# stm32custompcb_schematic.net
KiCad netlist of a schematic drawn in Altium Designer
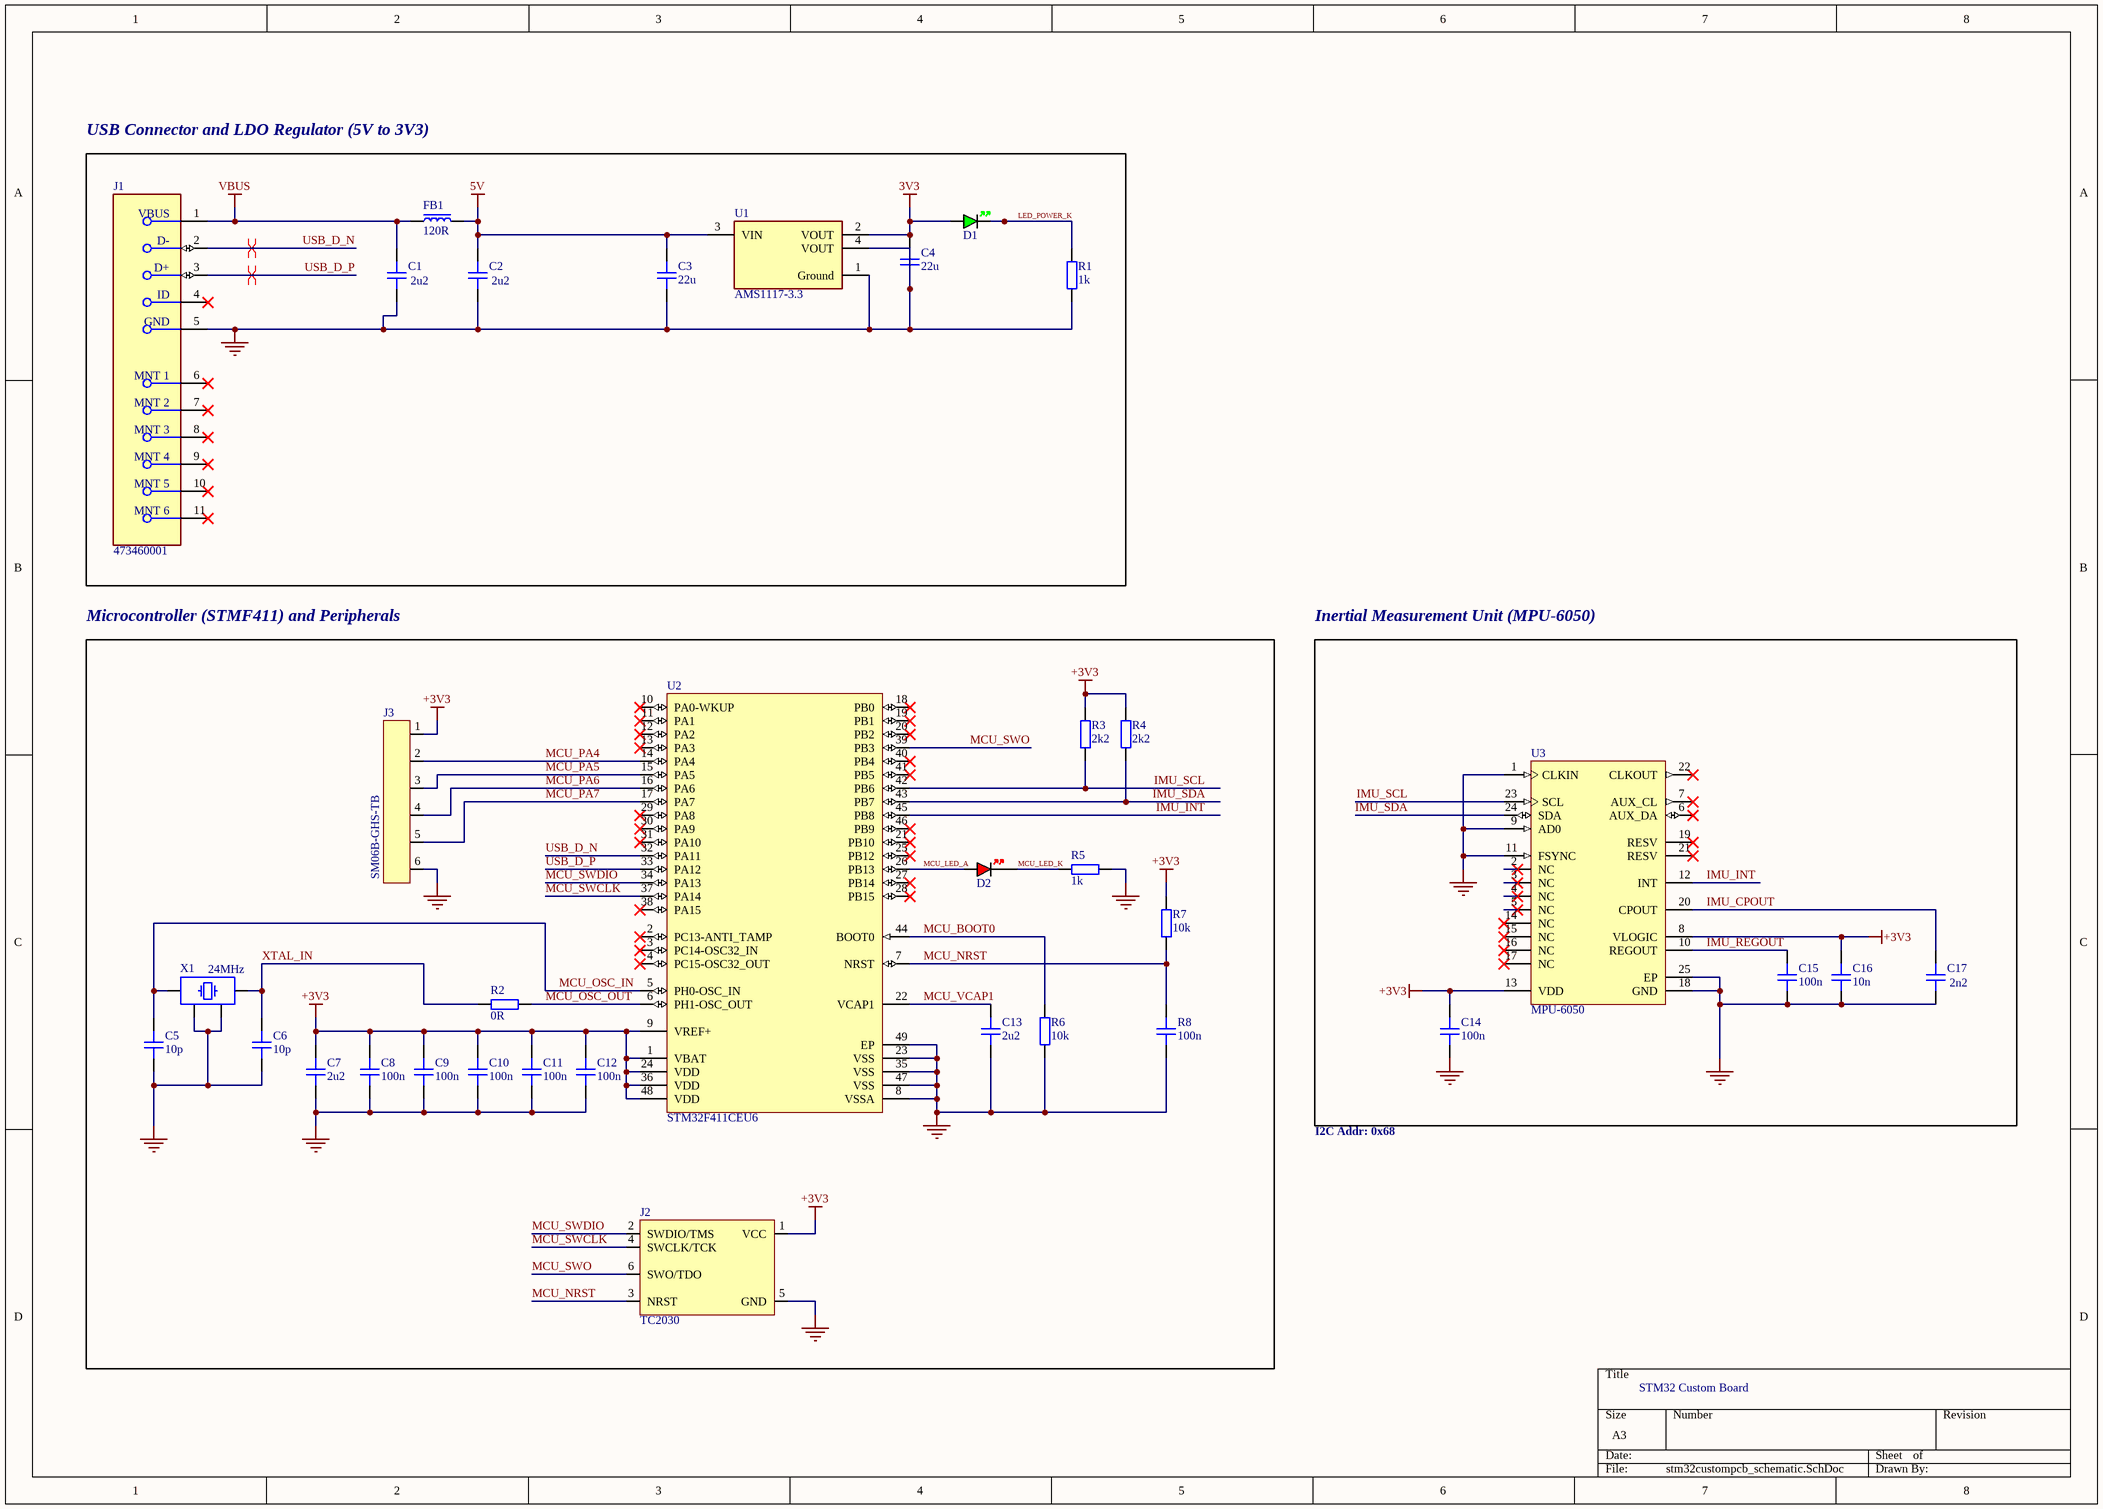
[diagram p0: stm32custompcb_schematic.SchDoc]

(export (version "E")
  (design (tool "Eeschema 10.0.6"))
  (components
    (comp (ref "C1")
      (value "2u2")
      (footprint "CAP_0402")
      (description "Capacitor SMD 0402")
      (libsource (lib "Schematic-Lib-PhilsLab") (part "CAP_0402"))
    )
    (comp (ref "C2")
      (value "2u2")
      (footprint "CAP_0402")
      (description "Capacitor SMD 0402")
      (libsource (lib "Schematic-Lib-PhilsLab") (part "CAP_0402"))
    )
    (comp (ref "C3")
      (value "22u")
      (footprint "CAP_0805")
      (description "Capacitor SMD 0805")
      (libsource (lib "Schematic-Lib-PhilsLab") (part "CAP_0805"))
    )
    (comp (ref "C4")
      (value "22u")
      (footprint "CAP_0805")
      (description "Capacitor SMD 0805")
      (libsource (lib "Schematic-Lib-PhilsLab") (part "CAP_0805"))
    )
    (comp (ref "C5")
      (value "10p")
      (footprint "CAP_0402")
      (description "Capacitor SMD 0402")
      (libsource (lib "Schematic-Lib-PhilsLab") (part "CAP_0402"))
    )
    (comp (ref "C6")
      (value "10p")
      (footprint "CAP_0402")
      (description "Capacitor SMD 0402")
      (libsource (lib "Schematic-Lib-PhilsLab") (part "CAP_0402"))
    )
    (comp (ref "C7")
      (value "2u2")
      (footprint "CAP_0603")
      (description "Capacitor SMD 0603")
      (libsource (lib "Schematic-Lib-PhilsLab") (part "CAP_0603"))
    )
    (comp (ref "C8")
      (value "100n")
      (footprint "CAP_0402")
      (description "Capacitor SMD 0402")
      (libsource (lib "Schematic-Lib-PhilsLab") (part "CAP_0402"))
    )
    (comp (ref "C9")
      (value "100n")
      (footprint "CAP_0402")
      (description "Capacitor SMD 0402")
      (libsource (lib "Schematic-Lib-PhilsLab") (part "CAP_0402"))
    )
    (comp (ref "C10")
      (value "100n")
      (footprint "CAP_0402")
      (description "Capacitor SMD 0402")
      (libsource (lib "Schematic-Lib-PhilsLab") (part "CAP_0402"))
    )
    (comp (ref "C11")
      (value "100n")
      (footprint "CAP_0402")
      (description "Capacitor SMD 0402")
      (libsource (lib "Schematic-Lib-PhilsLab") (part "CAP_0402"))
    )
    (comp (ref "C12")
      (value "100n")
      (footprint "CAP_0402")
      (description "Capacitor SMD 0402")
      (libsource (lib "Schematic-Lib-PhilsLab") (part "CAP_0402"))
    )
    (comp (ref "C13")
      (value "2u2")
      (footprint "CAP_0603")
      (description "Capacitor SMD 0603")
      (libsource (lib "Schematic-Lib-PhilsLab") (part "CAP_0603"))
    )
    (comp (ref "C14")
      (value "100n")
      (footprint "CAP_0402")
      (description "Capacitor SMD 0402")
      (libsource (lib "Schematic-Lib-PhilsLab") (part "CAP_0402"))
    )
    (comp (ref "C15")
      (value "100n")
      (footprint "CAP_0402")
      (description "Capacitor SMD 0402")
      (libsource (lib "Schematic-Lib-PhilsLab") (part "CAP_0402"))
    )
    (comp (ref "C16")
      (value "10n")
      (footprint "CAP_0402")
      (description "Capacitor SMD 0402")
      (libsource (lib "Schematic-Lib-PhilsLab") (part "CAP_0402"))
    )
    (comp (ref "C17")
      (value "2n2")
      (footprint "CAP_0402")
      (description "Capacitor SMD 0402")
      (libsource (lib "Schematic-Lib-PhilsLab") (part "CAP_0402"))
    )
    (comp (ref "D1")
      (value "GREEN")
      (footprint "LED_0402_GREEN")
      (description "LED 0402 GREEN SMD")
      (libsource (lib "Schematic-Lib-PhilsLab") (part "LED_0402_GREEN"))
    )
    (comp (ref "D2")
      (value "RED")
      (footprint "LED_0402_RED")
      (description "LED 0402 RED SMD")
      (libsource (lib "Schematic-Lib-PhilsLab") (part "LED_0402_RED"))
    )
    (comp (ref "FB1")
      (value "120R")
      (footprint "FB_0603")
      (description "Ferrite Bead SMD 0603")
      (libsource (lib "Schematic-Lib-PhilsLab") (part "FB_0603"))
    )
    (comp (ref "J1")
      (value "473460001")
      (footprint "FP-473460001-MFG")
      (description "CONN RCPT USB2.0 MICRO B SMD R/A")
      (fields
        (field (name "OCTOPART") "https://octopart.com/47346-0001-molex-7164928")
        (field (name "MANUFACTURER") "Molex")
      )
      (libsource (lib "Altium Content Vault") (part "53ae1f1d9b557310b43ca686e5bb76a"))
    )
    (comp (ref "J2")
      (value "TC2030")
      (footprint "TC2030-FP")
      (description "Tag-Connect No-Solder SWD Debug Connector DO NOT PLACE")
      (fields (field (name "MANUFACTURER") "Tag-Connect"))
      (libsource (lib "Schematic-Lib-PhilsLab") (part "TC2030"))
    )
    (comp (ref "J3")
      (value "SM06B-GHS-TB")
      (footprint "SM06B-GHS-TB")
      (description "Header Connector 6 Position 1.25MM Pitch SMD Horizontal JST GH")
      (fields (field (name "MANUFACTURER") "JST"))
      (libsource (lib "Schematic-Lib-PhilsLab") (part "SM06B-GHS-TB"))
    )
    (comp (ref "R1")
      (value "1k")
      (footprint "RES_0402")
      (description "Resistor SMD 0402")
      (libsource (lib "Schematic-Lib-PhilsLab") (part "RES_0402"))
    )
    (comp (ref "R2")
      (value "0R")
      (footprint "RES_0402")
      (description "Resistor SMD 0402")
      (libsource (lib "Schematic-Lib-PhilsLab") (part "RES_0402"))
    )
    (comp (ref "R3")
      (value "2k2")
      (footprint "RES_0402")
      (description "Resistor SMD 0402")
      (libsource (lib "Schematic-Lib-PhilsLab") (part "RES_0402"))
    )
    (comp (ref "R4")
      (value "2k2")
      (footprint "RES_0402")
      (description "Resistor SMD 0402")
      (libsource (lib "Schematic-Lib-PhilsLab") (part "RES_0402"))
    )
    (comp (ref "R5")
      (value "1k")
      (footprint "RES_0402")
      (description "Resistor SMD 0402")
      (libsource (lib "Schematic-Lib-PhilsLab") (part "RES_0402"))
    )
    (comp (ref "R6")
      (value "10k")
      (footprint "RES_0402")
      (description "Resistor SMD 0402")
      (libsource (lib "Schematic-Lib-PhilsLab") (part "RES_0402"))
    )
    (comp (ref "R7")
      (value "10k")
      (footprint "RES_0402")
      (description "Resistor SMD 0402")
      (libsource (lib "Schematic-Lib-PhilsLab") (part "RES_0402"))
    )
    (comp (ref "R8")
      (value "100n")
      (footprint "CAP_0402")
      (description "Capacitor SMD 0402")
      (libsource (lib "Schematic-Lib-PhilsLab") (part "CAP_0402"))
    )
    (comp (ref "U1")
      (value "AMS1117-3.3")
      (footprint "FP-AMS1117-IPC_C")
      (description "LDO Voltage Regulators 1A, 3.3V")
      (fields
        (field (name "OCTOPART") "https://octopart.com/ams1117-3.3-advanced+monolithic+systems-25899300")
        (field (name "MANUFACTURER") "Advanced Monolithic Systems")
      )
      (libsource (lib "Altium Content Vault") (part "8bdbb5f8e77002000e30dd2845d0354"))
    )
    (comp (ref "U2")
      (value "STM32F411CEU6")
      (footprint "STM-UFQFPN48_L")
      (libsource (lib "Altium Content Vault") (part "MC-ARM-STM32F411-UFQFPN48"))
    )
    (comp (ref "U3")
      (value "MPU-6050")
      (footprint "IS-QFN-24_V")
      (fields (field (name "MANUFACTURER") "InvenSense"))
      (libsource (lib "Altium Content Vault") (part "IS-MPU-6050-QFN-24"))
    )
    (comp (ref "X1")
      (value "24MHz")
      (footprint "XTAL_3225")
      (description "Crystal SMD 24MHz 10PPM 7pF 3225")
      (fields
        (field (name "MANUFACTURER") "Epson")
        (field (name "MANUFACTURER PART NUMBER") "TSX-3225 24.0000MF15X-AC")
      )
      (libsource (lib "Schematic-Lib-PhilsLab") (part "TSX-3225_24.0000MF15X-AC"))
    )
  )
  (nets
    (net (code "1") (name "+3V3") (class "Default")
      (node (ref "C10") (pin "2") (pinfunction "2_2") (pintype "passive"))
      (node (ref "C11") (pin "2") (pinfunction "2_2") (pintype "passive"))
      (node (ref "C12") (pin "2") (pinfunction "2_2") (pintype "passive"))
      (node (ref "C14") (pin "2") (pinfunction "2_2") (pintype "passive"))
      (node (ref "C16") (pin "2") (pinfunction "2_2") (pintype "passive"))
      (node (ref "C7") (pin "1") (pinfunction "1_1") (pintype "passive"))
      (node (ref "C8") (pin "2") (pinfunction "2_2") (pintype "passive"))
      (node (ref "C9") (pin "2") (pinfunction "2_2") (pintype "passive"))
      (node (ref "J2") (pin "1") (pinfunction "VCC_1") (pintype "passive"))
      (node (ref "J3") (pin "1") (pinfunction "1_1") (pintype "passive"))
      (node (ref "R3") (pin "2") (pinfunction "2_2") (pintype "passive"))
      (node (ref "R4") (pin "2") (pinfunction "2_2") (pintype "passive"))
      (node (ref "R7") (pin "2") (pinfunction "2_2") (pintype "passive"))
      (node (ref "U2") (pin "1") (pinfunction "VBAT_1") (pintype "power_in"))
      (node (ref "U2") (pin "24") (pinfunction "VDD_24") (pintype "power_in"))
      (node (ref "U2") (pin "36") (pinfunction "VDD_36") (pintype "power_in"))
      (node (ref "U2") (pin "48") (pinfunction "VDD_48") (pintype "power_in"))
      (node (ref "U2") (pin "9") (pinfunction "VREF+_9") (pintype "power_in"))
      (node (ref "U3") (pin "13") (pinfunction "VDD_13") (pintype "power_in"))
      (node (ref "U3") (pin "8") (pinfunction "VLOGIC_8") (pintype "power_in"))
    )
    (net (code "2") (name "/IMU_CPOUT") (class "Default")
      (node (ref "C17") (pin "2") (pinfunction "2_2") (pintype "passive"))
      (node (ref "U3") (pin "20") (pinfunction "CPOUT_20") (pintype "passive"))
    )
    (net (code "3") (name "/IMU_INT") (class "Default")
      (node (ref "U2") (pin "45") (pinfunction "PB8_45") (pintype "bidirectional"))
      (node (ref "U3") (pin "12") (pinfunction "INT_12") (pintype "open_collector"))
    )
    (net (code "4") (name "/IMU_REGOUT") (class "Default")
      (node (ref "C15") (pin "2") (pinfunction "2_2") (pintype "passive"))
      (node (ref "U3") (pin "10") (pinfunction "REGOUT_10") (pintype "passive"))
    )
    (net (code "5") (name "/IMU_SCL") (class "Default")
      (node (ref "R3") (pin "1") (pinfunction "1_1") (pintype "passive"))
      (node (ref "U2") (pin "42") (pinfunction "PB6_42") (pintype "bidirectional"))
      (node (ref "U3") (pin "23") (pinfunction "SCL_23") (pintype "input"))
    )
    (net (code "6") (name "/IMU_SDA") (class "Default")
      (node (ref "R4") (pin "1") (pinfunction "1_1") (pintype "passive"))
      (node (ref "U2") (pin "43") (pinfunction "PB7_43") (pintype "bidirectional"))
      (node (ref "U3") (pin "24") (pinfunction "SDA_24") (pintype "bidirectional"))
    )
    (net (code "7") (name "/LED_POWER_K") (class "Default")
      (node (ref "D1") (pin "K") (pinfunction "K_K") (pintype "passive"))
      (node (ref "R1") (pin "2") (pinfunction "2_2") (pintype "passive"))
    )
    (net (code "8") (name "/MCU_BOOT0") (class "Default")
      (node (ref "R6") (pin "2") (pinfunction "2_2") (pintype "passive"))
      (node (ref "U2") (pin "44") (pinfunction "BOOT0_44") (pintype "input"))
    )
    (net (code "9") (name "/MCU_LED_A") (class "Default")
      (node (ref "D2") (pin "A") (pinfunction "A_A") (pintype "passive"))
      (node (ref "U2") (pin "26") (pinfunction "PB13_26") (pintype "bidirectional"))
    )
    (net (code "10") (name "/MCU_LED_K") (class "Default")
      (node (ref "D2") (pin "K") (pinfunction "K_K") (pintype "passive"))
      (node (ref "R5") (pin "2") (pinfunction "2_2") (pintype "passive"))
    )
    (net (code "11") (name "/MCU_NRST") (class "Default")
      (node (ref "J2") (pin "3") (pinfunction "NRST_3") (pintype "passive"))
      (node (ref "R7") (pin "1") (pinfunction "1_1") (pintype "passive"))
      (node (ref "R8") (pin "2") (pinfunction "2_2") (pintype "passive"))
      (node (ref "U2") (pin "7") (pinfunction "NRST_7") (pintype "bidirectional"))
    )
    (net (code "12") (name "/MCU_OSC_IN") (class "Default")
      (node (ref "C5") (pin "2") (pinfunction "2_2") (pintype "passive"))
      (node (ref "U2") (pin "5") (pinfunction "PH0-OSC_IN_5") (pintype "bidirectional"))
      (node (ref "X1") (pin "1") (pinfunction "1_1") (pintype "passive"))
    )
    (net (code "13") (name "/MCU_OSC_OUT") (class "Default")
      (node (ref "R2") (pin "2") (pinfunction "2_2") (pintype "passive"))
      (node (ref "U2") (pin "6") (pinfunction "PH1-OSC_OUT_6") (pintype "bidirectional"))
    )
    (net (code "14") (name "/MCU_PA4") (class "Default")
      (node (ref "J3") (pin "2") (pinfunction "2_2") (pintype "passive"))
      (node (ref "U2") (pin "14") (pinfunction "PA4_14") (pintype "bidirectional"))
    )
    (net (code "15") (name "/MCU_PA5") (class "Default")
      (node (ref "J3") (pin "3") (pinfunction "3_3") (pintype "passive"))
      (node (ref "U2") (pin "15") (pinfunction "PA5_15") (pintype "bidirectional"))
    )
    (net (code "16") (name "/MCU_PA6") (class "Default")
      (node (ref "J3") (pin "4") (pinfunction "4_4") (pintype "passive"))
      (node (ref "U2") (pin "16") (pinfunction "PA6_16") (pintype "bidirectional"))
    )
    (net (code "17") (name "/MCU_PA7") (class "Default")
      (node (ref "J3") (pin "5") (pinfunction "5_5") (pintype "passive"))
      (node (ref "U2") (pin "17") (pinfunction "PA7_17") (pintype "bidirectional"))
    )
    (net (code "18") (name "/MCU_SWCLK") (class "Default")
      (node (ref "J2") (pin "4") (pinfunction "SWCLK/TCK_4") (pintype "passive"))
      (node (ref "U2") (pin "37") (pinfunction "PA14_37") (pintype "bidirectional"))
    )
    (net (code "19") (name "/MCU_SWDIO") (class "Default")
      (node (ref "J2") (pin "2") (pinfunction "SWDIO/TMS_2") (pintype "passive"))
      (node (ref "U2") (pin "34") (pinfunction "PA13_34") (pintype "bidirectional"))
    )
    (net (code "20") (name "/MCU_SWO") (class "Default")
      (node (ref "J2") (pin "6") (pinfunction "SWO/TDO_6") (pintype "passive"))
      (node (ref "U2") (pin "39") (pinfunction "PB3_39") (pintype "bidirectional"))
    )
    (net (code "21") (name "/MCU_VCAP1") (class "Default")
      (node (ref "C13") (pin "1") (pinfunction "1_1") (pintype "passive"))
      (node (ref "U2") (pin "22") (pinfunction "VCAP1_22") (pintype "passive"))
    )
    (net (code "22") (name "/USB_D_N") (class "Default")
      (node (ref "J1") (pin "2") (pinfunction "D-_2") (pintype "bidirectional"))
      (node (ref "U2") (pin "32") (pinfunction "PA11_32") (pintype "bidirectional"))
    )
    (net (code "23") (name "/USB_D_P") (class "Default")
      (node (ref "J1") (pin "3") (pinfunction "D+_3") (pintype "bidirectional"))
      (node (ref "U2") (pin "33") (pinfunction "PA12_33") (pintype "bidirectional"))
    )
    (net (code "24") (name "/XTAL_IN") (class "Default")
      (node (ref "C6") (pin "2") (pinfunction "2_2") (pintype "passive"))
      (node (ref "R2") (pin "1") (pinfunction "1_1") (pintype "passive"))
      (node (ref "X1") (pin "3") (pinfunction "3_3") (pintype "passive"))
    )
    (net (code "25") (name "3V3") (class "Default")
      (node (ref "C4") (pin "1") (pinfunction "1_1") (pintype "passive"))
      (node (ref "D1") (pin "A") (pinfunction "A_A") (pintype "passive"))
      (node (ref "U1") (pin "2") (pinfunction "VOUT_2") (pintype "passive"))
    )
    (net (code "26") (name "5V") (class "Default")
      (node (ref "C2") (pin "2") (pinfunction "2_2") (pintype "passive"))
      (node (ref "C3") (pin "1") (pinfunction "1_1") (pintype "passive"))
      (node (ref "FB1") (pin "2") (pinfunction "2_2") (pintype "passive"))
      (node (ref "U1") (pin "3") (pinfunction "VIN_3") (pintype "power_in"))
    )
    (net (code "27") (name "GND") (class "Default")
      (node (ref "C1") (pin "1") (pinfunction "1_1") (pintype "passive"))
      (node (ref "C10") (pin "1") (pinfunction "1_1") (pintype "passive"))
      (node (ref "C11") (pin "1") (pinfunction "1_1") (pintype "passive"))
      (node (ref "C12") (pin "1") (pinfunction "1_1") (pintype "passive"))
      (node (ref "C13") (pin "2") (pinfunction "2_2") (pintype "passive"))
      (node (ref "C14") (pin "1") (pinfunction "1_1") (pintype "passive"))
      (node (ref "C15") (pin "1") (pinfunction "1_1") (pintype "passive"))
      (node (ref "C16") (pin "1") (pinfunction "1_1") (pintype "passive"))
      (node (ref "C17") (pin "1") (pinfunction "1_1") (pintype "passive"))
      (node (ref "C2") (pin "1") (pinfunction "1_1") (pintype "passive"))
      (node (ref "C3") (pin "2") (pinfunction "2_2") (pintype "passive"))
      (node (ref "C4") (pin "2") (pinfunction "2_2") (pintype "passive"))
      (node (ref "C5") (pin "1") (pinfunction "1_1") (pintype "passive"))
      (node (ref "C6") (pin "1") (pinfunction "1_1") (pintype "passive"))
      (node (ref "C7") (pin "2") (pinfunction "2_2") (pintype "passive"))
      (node (ref "C8") (pin "1") (pinfunction "1_1") (pintype "passive"))
      (node (ref "C9") (pin "1") (pinfunction "1_1") (pintype "passive"))
      (node (ref "J1") (pin "5") (pinfunction "GND_5") (pintype "power_in"))
      (node (ref "J2") (pin "5") (pinfunction "GND_5") (pintype "passive"))
      (node (ref "J3") (pin "6") (pinfunction "6_6") (pintype "passive"))
      (node (ref "R1") (pin "1") (pinfunction "1_1") (pintype "passive"))
      (node (ref "R5") (pin "1") (pinfunction "1_1") (pintype "passive"))
      (node (ref "R6") (pin "1") (pinfunction "1_1") (pintype "passive"))
      (node (ref "R8") (pin "1") (pinfunction "1_1") (pintype "passive"))
      (node (ref "U1") (pin "1") (pinfunction "Ground_1") (pintype "power_in"))
      (node (ref "U1") (pin "4") (pinfunction "VOUT_4") (pintype "passive"))
      (node (ref "U2") (pin "23") (pinfunction "VSS_23") (pintype "power_in"))
      (node (ref "U2") (pin "35") (pinfunction "VSS_35") (pintype "power_in"))
      (node (ref "U2") (pin "47") (pinfunction "VSS_47") (pintype "power_in"))
      (node (ref "U2") (pin "49") (pinfunction "EP_49") (pintype "power_in"))
      (node (ref "U2") (pin "8") (pinfunction "VSSA_8") (pintype "power_in"))
      (node (ref "U3") (pin "1") (pinfunction "CLKIN_1") (pintype "input"))
      (node (ref "U3") (pin "11") (pinfunction "FSYNC_11") (pintype "input"))
      (node (ref "U3") (pin "18") (pinfunction "GND_18") (pintype "power_in"))
      (node (ref "U3") (pin "25") (pinfunction "EP_25") (pintype "power_in"))
      (node (ref "U3") (pin "9") (pinfunction "AD0_9") (pintype "input"))
      (node (ref "X1") (pin "2") (pinfunction "2_2") (pintype "passive"))
      (node (ref "X1") (pin "4") (pinfunction "4_4") (pintype "passive"))
    )
    (net (code "28") (name "VBUS") (class "Default")
      (node (ref "C1") (pin "2") (pinfunction "2_2") (pintype "passive"))
      (node (ref "FB1") (pin "1") (pinfunction "1_1") (pintype "passive"))
      (node (ref "J1") (pin "1") (pinfunction "VBUS_1") (pintype "power_in"))
    )
    (net (code "29") (name "unconnected-(J1-ID-Pad4)") (class "Default")
      (node (ref "J1") (pin "4") (pinfunction "ID_4") (pintype "passive+no_connect"))
    )
    (net (code "30") (name "unconnected-(J1-MNT_1-Pad6)") (class "Default")
      (node (ref "J1") (pin "6") (pinfunction "MNT_1_6") (pintype "passive+no_connect"))
    )
    (net (code "31") (name "unconnected-(J1-MNT_2-Pad7)") (class "Default")
      (node (ref "J1") (pin "7") (pinfunction "MNT_2_7") (pintype "passive+no_connect"))
    )
    (net (code "32") (name "unconnected-(J1-MNT_3-Pad8)") (class "Default")
      (node (ref "J1") (pin "8") (pinfunction "MNT_3_8") (pintype "passive+no_connect"))
    )
    (net (code "33") (name "unconnected-(J1-MNT_4-Pad9)") (class "Default")
      (node (ref "J1") (pin "9") (pinfunction "MNT_4_9") (pintype "passive+no_connect"))
    )
    (net (code "34") (name "unconnected-(J1-MNT_5-Pad10)") (class "Default")
      (node (ref "J1") (pin "10") (pinfunction "MNT_5_10") (pintype "passive+no_connect"))
    )
    (net (code "35") (name "unconnected-(J1-MNT_6-Pad11)") (class "Default")
      (node (ref "J1") (pin "11") (pinfunction "MNT_6_11") (pintype "passive+no_connect"))
    )
    (net (code "36") (name "unconnected-(U2-PA0-WKUP-Pad10)") (class "Default")
      (node (ref "U2") (pin "10") (pinfunction "PA0-WKUP_10") (pintype "bidirectional+no_connect"))
    )
    (net (code "37") (name "unconnected-(U2-PA1-Pad11)") (class "Default")
      (node (ref "U2") (pin "11") (pinfunction "PA1_11") (pintype "bidirectional+no_connect"))
    )
    (net (code "38") (name "unconnected-(U2-PA2-Pad12)") (class "Default")
      (node (ref "U2") (pin "12") (pinfunction "PA2_12") (pintype "bidirectional+no_connect"))
    )
    (net (code "39") (name "unconnected-(U2-PA3-Pad13)") (class "Default")
      (node (ref "U2") (pin "13") (pinfunction "PA3_13") (pintype "bidirectional+no_connect"))
    )
    (net (code "40") (name "unconnected-(U2-PA8-Pad29)") (class "Default")
      (node (ref "U2") (pin "29") (pinfunction "PA8_29") (pintype "bidirectional+no_connect"))
    )
    (net (code "41") (name "unconnected-(U2-PA9-Pad30)") (class "Default")
      (node (ref "U2") (pin "30") (pinfunction "PA9_30") (pintype "bidirectional+no_connect"))
    )
    (net (code "42") (name "unconnected-(U2-PA10-Pad31)") (class "Default")
      (node (ref "U2") (pin "31") (pinfunction "PA10_31") (pintype "bidirectional+no_connect"))
    )
    (net (code "43") (name "unconnected-(U2-PA15-Pad38)") (class "Default")
      (node (ref "U2") (pin "38") (pinfunction "PA15_38") (pintype "bidirectional+no_connect"))
    )
    (net (code "44") (name "unconnected-(U2-PB0-Pad18)") (class "Default")
      (node (ref "U2") (pin "18") (pinfunction "PB0_18") (pintype "bidirectional+no_connect"))
    )
    (net (code "45") (name "unconnected-(U2-PB1-Pad19)") (class "Default")
      (node (ref "U2") (pin "19") (pinfunction "PB1_19") (pintype "bidirectional+no_connect"))
    )
    (net (code "46") (name "unconnected-(U2-PB2-Pad20)") (class "Default")
      (node (ref "U2") (pin "20") (pinfunction "PB2_20") (pintype "bidirectional+no_connect"))
    )
    (net (code "47") (name "unconnected-(U2-PB4-Pad40)") (class "Default")
      (node (ref "U2") (pin "40") (pinfunction "PB4_40") (pintype "bidirectional+no_connect"))
    )
    (net (code "48") (name "unconnected-(U2-PB5-Pad41)") (class "Default")
      (node (ref "U2") (pin "41") (pinfunction "PB5_41") (pintype "bidirectional+no_connect"))
    )
    (net (code "49") (name "unconnected-(U2-PB9-Pad46)") (class "Default")
      (node (ref "U2") (pin "46") (pinfunction "PB9_46") (pintype "bidirectional+no_connect"))
    )
    (net (code "50") (name "unconnected-(U2-PB10-Pad21)") (class "Default")
      (node (ref "U2") (pin "21") (pinfunction "PB10_21") (pintype "bidirectional+no_connect"))
    )
    (net (code "51") (name "unconnected-(U2-PB12-Pad25)") (class "Default")
      (node (ref "U2") (pin "25") (pinfunction "PB12_25") (pintype "bidirectional+no_connect"))
    )
    (net (code "52") (name "unconnected-(U2-PB14-Pad27)") (class "Default")
      (node (ref "U2") (pin "27") (pinfunction "PB14_27") (pintype "bidirectional+no_connect"))
    )
    (net (code "53") (name "unconnected-(U2-PB15-Pad28)") (class "Default")
      (node (ref "U2") (pin "28") (pinfunction "PB15_28") (pintype "bidirectional+no_connect"))
    )
    (net (code "54") (name "unconnected-(U2-PC13-ANTI_TAMP-Pad2)") (class "Default")
      (node (ref "U2") (pin "2") (pinfunction "PC13-ANTI_TAMP_2") (pintype "bidirectional+no_connect"))
    )
    (net (code "55") (name "unconnected-(U2-PC14-OSC32_IN-Pad3)") (class "Default")
      (node (ref "U2") (pin "3") (pinfunction "PC14-OSC32_IN_3") (pintype "bidirectional+no_connect"))
    )
    (net (code "56") (name "unconnected-(U2-PC15-OSC32_OUT-Pad4)") (class "Default")
      (node (ref "U2") (pin "4") (pinfunction "PC15-OSC32_OUT_4") (pintype "bidirectional+no_connect"))
    )
    (net (code "57") (name "unconnected-(U3-AUX_CL-Pad7)") (class "Default")
      (node (ref "U3") (pin "7") (pinfunction "AUX_CL_7") (pintype "output+no_connect"))
    )
    (net (code "58") (name "unconnected-(U3-AUX_DA-Pad6)") (class "Default")
      (node (ref "U3") (pin "6") (pinfunction "AUX_DA_6") (pintype "bidirectional+no_connect"))
    )
    (net (code "59") (name "unconnected-(U3-CLKOUT-Pad22)") (class "Default")
      (node (ref "U3") (pin "22") (pinfunction "CLKOUT_22") (pintype "output+no_connect"))
    )
    (net (code "60") (name "unconnected-(U3-NC-Pad2)") (class "Default")
      (node (ref "U3") (pin "2") (pinfunction "NC_2") (pintype "passive+no_connect"))
    )
    (net (code "61") (name "unconnected-(U3-NC-Pad3)") (class "Default")
      (node (ref "U3") (pin "3") (pinfunction "NC_3") (pintype "passive+no_connect"))
    )
    (net (code "62") (name "unconnected-(U3-NC-Pad4)") (class "Default")
      (node (ref "U3") (pin "4") (pinfunction "NC_4") (pintype "passive+no_connect"))
    )
    (net (code "63") (name "unconnected-(U3-NC-Pad5)") (class "Default")
      (node (ref "U3") (pin "5") (pinfunction "NC_5") (pintype "passive+no_connect"))
    )
    (net (code "64") (name "unconnected-(U3-NC-Pad14)") (class "Default")
      (node (ref "U3") (pin "14") (pinfunction "NC_14") (pintype "passive+no_connect"))
    )
    (net (code "65") (name "unconnected-(U3-NC-Pad15)") (class "Default")
      (node (ref "U3") (pin "15") (pinfunction "NC_15") (pintype "passive+no_connect"))
    )
    (net (code "66") (name "unconnected-(U3-NC-Pad16)") (class "Default")
      (node (ref "U3") (pin "16") (pinfunction "NC_16") (pintype "passive+no_connect"))
    )
    (net (code "67") (name "unconnected-(U3-NC-Pad17)") (class "Default")
      (node (ref "U3") (pin "17") (pinfunction "NC_17") (pintype "passive+no_connect"))
    )
    (net (code "68") (name "unconnected-(U3-RESV-Pad19)") (class "Default")
      (node (ref "U3") (pin "19") (pinfunction "RESV_19") (pintype "passive+no_connect"))
    )
    (net (code "69") (name "unconnected-(U3-RESV-Pad21)") (class "Default")
      (node (ref "U3") (pin "21") (pinfunction "RESV_21") (pintype "passive+no_connect"))
    )
  )
)
